# manette_temp.net
KiCad netlist of a schematic drawn in Altium Designer
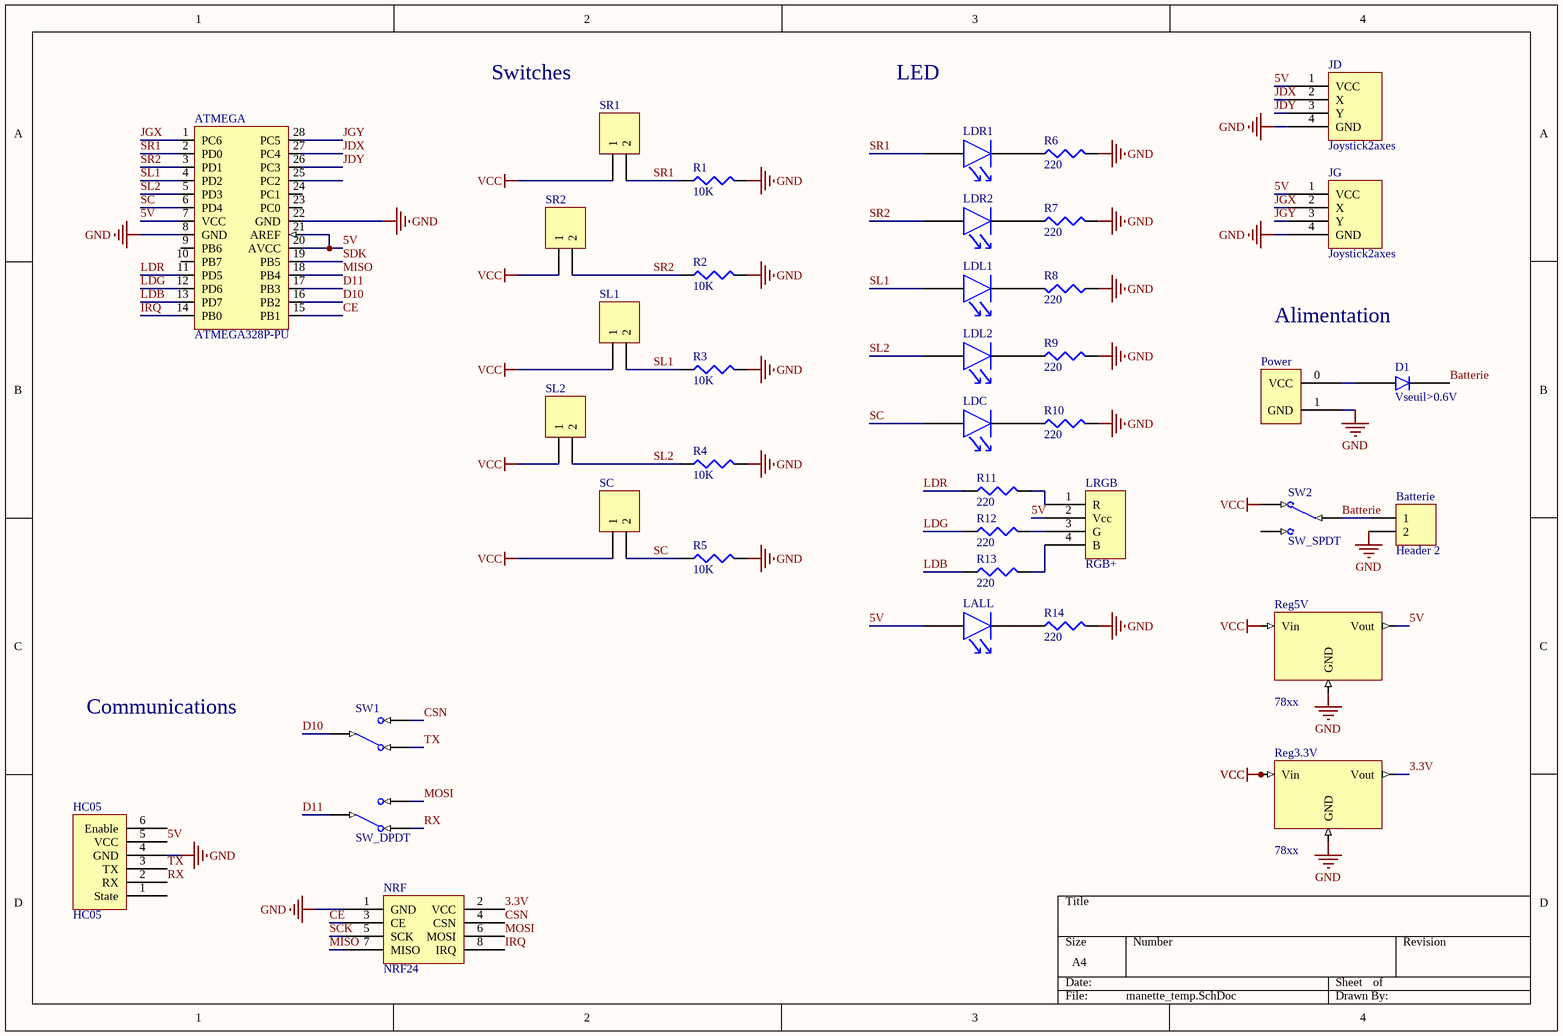
[diagram p0: manette_temp.SchDoc]

(export (version "E")
  (design (tool "Eeschema 10.0.6"))
  (components
    (comp (ref "ATMEGA")
      (value "ATMEGA328P-PU")
      (footprint "DIP28_300")
      (libsource (lib "ISEN_basics") (part "ATMEGA328P-PU"))
    )
    (comp (ref "Batterie")
      (value "Header 2")
      (footprint "HDR1X2")
      (description "Header, 2-Pin")
      (fields (field (name "PUBLISHER") "Altium Limited"))
      (libsource (lib "Miscellaneous Connectors") (part "Header 2"))
    )
    (comp (ref "D1")
      (value "Vseuil>0.6V")
      (footprint "SMA")
      (description "diode usage général")
      (libsource (lib "ISEN_basics") (part "DIODE"))
    )
    (comp (ref "HC05") (value "HC05") (footprint "HC05") (libsource (lib "HC05") (part "HC05")))
    (comp (ref "JD")
      (value "Joystick2axes")
      (footprint "Joystick2axes")
      (libsource (lib "Library") (part "Joystick2axes"))
    )
    (comp (ref "JG")
      (value "Joystick2axes")
      (footprint "Joystick2axes")
      (libsource (lib "Library") (part "Joystick2axes"))
    )
    (comp (ref "LALL")
      (value "comment")
      (footprint "LED5")
      (description "LED 5mm/3mm/CMS")
      (libsource (lib "ISEN_basics") (part "LED"))
    )
    (comp (ref "LDC")
      (value "comment")
      (footprint "LED0805")
      (description "LED 5mm/3mm/CMS")
      (libsource (lib "ISEN_basics") (part "LED"))
    )
    (comp (ref "LDL1")
      (value "comment")
      (footprint "LED0805")
      (description "LED 5mm/3mm/CMS")
      (libsource (lib "ISEN_basics") (part "LED"))
    )
    (comp (ref "LDL2")
      (value "comment")
      (footprint "LED0805")
      (description "LED 5mm/3mm/CMS")
      (libsource (lib "ISEN_basics") (part "LED"))
    )
    (comp (ref "LDR1")
      (value "comment")
      (footprint "LED0805")
      (description "LED 5mm/3mm/CMS")
      (libsource (lib "ISEN_basics") (part "LED"))
    )
    (comp (ref "LDR2")
      (value "comment")
      (footprint "LED0805")
      (description "LED 5mm/3mm/CMS")
      (libsource (lib "ISEN_basics") (part "LED"))
    )
    (comp (ref "LRGB") (value "RGB+") (footprint "Led RGB") (libsource (lib "Library") (part "RGB+")))
    (comp (ref "NRF") (value "NRF24") (footprint "NRF24") (libsource (lib "Library") (part "NRF24")))
    (comp (ref "Power")
      (value "Connecteur Power")
      (footprint "Connecteur Power")
      (libsource (lib "Connectorpower") (part "Connecteur Power"))
    )
    (comp (ref "R1")
      (value "10K")
      (footprint "0805")
      (description "resistance")
      (fields (field (name "Comment") "RES"))
      (libsource (lib "ISEN_basics") (part "RES"))
    )
    (comp (ref "R2")
      (value "10K")
      (footprint "0805")
      (description "resistance")
      (fields (field (name "Comment") "RES"))
      (libsource (lib "ISEN_basics") (part "RES"))
    )
    (comp (ref "R3")
      (value "10K")
      (footprint "0805")
      (description "resistance")
      (fields (field (name "Comment") "RES"))
      (libsource (lib "ISEN_basics") (part "RES"))
    )
    (comp (ref "R4")
      (value "10K")
      (footprint "0805")
      (description "resistance")
      (fields (field (name "Comment") "RES"))
      (libsource (lib "ISEN_basics") (part "RES"))
    )
    (comp (ref "R5")
      (value "10K")
      (footprint "0805")
      (description "resistance")
      (fields (field (name "Comment") "RES"))
      (libsource (lib "ISEN_basics") (part "RES"))
    )
    (comp (ref "R6")
      (value "220")
      (footprint "0805")
      (description "resistance")
      (fields (field (name "Comment") "RES"))
      (libsource (lib "ISEN_basics") (part "RES"))
    )
    (comp (ref "R7")
      (value "220")
      (footprint "0805")
      (description "resistance")
      (fields (field (name "Comment") "RES"))
      (libsource (lib "ISEN_basics") (part "RES"))
    )
    (comp (ref "R8")
      (value "220")
      (footprint "0805")
      (description "resistance")
      (fields (field (name "Comment") "RES"))
      (libsource (lib "ISEN_basics") (part "RES"))
    )
    (comp (ref "R9")
      (value "220")
      (footprint "0805")
      (description "resistance")
      (fields (field (name "Comment") "RES"))
      (libsource (lib "ISEN_basics") (part "RES"))
    )
    (comp (ref "R10")
      (value "220")
      (footprint "0805")
      (description "resistance")
      (fields (field (name "Comment") "RES"))
      (libsource (lib "ISEN_basics") (part "RES"))
    )
    (comp (ref "R11")
      (value "220")
      (footprint "0805")
      (description "resistance")
      (fields (field (name "Comment") "RES"))
      (libsource (lib "ISEN_basics") (part "RES"))
    )
    (comp (ref "R12")
      (value "220")
      (footprint "0805")
      (description "resistance")
      (fields (field (name "Comment") "RES"))
      (libsource (lib "ISEN_basics") (part "RES"))
    )
    (comp (ref "R13")
      (value "220")
      (footprint "0805")
      (description "resistance")
      (fields (field (name "Comment") "RES"))
      (libsource (lib "ISEN_basics") (part "RES"))
    )
    (comp (ref "R14")
      (value "220")
      (footprint "0805")
      (description "resistance")
      (fields (field (name "Comment") "RES"))
      (libsource (lib "ISEN_basics") (part "RES"))
    )
    (comp (ref "Reg3.3V")
      (value "78xx")
      (footprint "TO252")
      (description "régulateur positif fixe")
      (libsource (lib "ISEN_basics") (part "REG_POS"))
    )
    (comp (ref "Reg5V")
      (value "78xx")
      (footprint "TO252")
      (description "régulateur positif fixe")
      (libsource (lib "ISEN_basics") (part "REG_POS"))
    )
    (comp (ref "SC")
      (value "Header 2")
      (footprint "HDR1X2")
      (description "Header, 2-Pin")
      (fields (field (name "PUBLISHER") "Altium Limited"))
      (libsource (lib "") (part "Header 2_1"))
    )
    (comp (ref "SL1")
      (value "Header 2")
      (footprint "HDR1X2")
      (description "Header, 2-Pin")
      (fields (field (name "PUBLISHER") "Altium Limited"))
      (libsource (lib "") (part "Header 2_1"))
    )
    (comp (ref "SL2")
      (value "Header 2")
      (footprint "HDR1X2")
      (description "Header, 2-Pin")
      (fields (field (name "PUBLISHER") "Altium Limited"))
      (libsource (lib "") (part "Header 2_1"))
    )
    (comp (ref "SR1")
      (value "Header 2")
      (footprint "HDR1X2")
      (description "Header, 2-Pin")
      (fields (field (name "PUBLISHER") "Altium Limited"))
      (libsource (lib "") (part "Header 2_1"))
    )
    (comp (ref "SR2")
      (value "Header 2")
      (footprint "HDR1X2")
      (description "Header, 2-Pin")
      (fields (field (name "PUBLISHER") "Altium Limited"))
      (libsource (lib "") (part "Header 2_1"))
    )
    (comp (ref "SW1")
      (value "SW_DPDT")
      (footprint "dpdt_bascule")
      (libsource (lib "ISEN_basics") (part "SW_DPDT"))
    )
    (comp (ref "SW2") (value "SW_SPDT") (footprint "1K2_V") (libsource (lib "ISEN_basics") (part "SW_SPDT")))
  )
  (nets
    (net (code "1") (name "/3.3V") (class "Default")
      (node (ref "NRF") (pin "2") (pinfunction "VCC_2") (pintype "passive"))
      (node (ref "Reg3.3V") (pin "3") (pinfunction "Vout_3") (pintype "output"))
    )
    (net (code "2") (name "/5V") (class "Default")
      (node (ref "ATMEGA") (pin "20") (pinfunction "AVCC_20") (pintype "power_in"))
      (node (ref "ATMEGA") (pin "21") (pinfunction "AREF_21") (pintype "input"))
      (node (ref "ATMEGA") (pin "7") (pinfunction "VCC_7") (pintype "power_in"))
      (node (ref "HC05") (pin "5") (pinfunction "VCC_5") (pintype "passive"))
      (node (ref "JD") (pin "1") (pinfunction "VCC_1") (pintype "passive"))
      (node (ref "JG") (pin "1") (pinfunction "VCC_1") (pintype "passive"))
      (node (ref "LALL") (pin "A") (pinfunction "8_A") (pintype "passive"))
      (node (ref "LRGB") (pin "2") (pinfunction "Vcc_2") (pintype "passive"))
      (node (ref "Reg5V") (pin "3") (pinfunction "Vout_3") (pintype "output"))
    )
    (net (code "3") (name "/Batterie") (class "Default")
      (node (ref "Batterie") (pin "1") (pinfunction "1_1") (pintype "passive"))
      (node (ref "D1") (pin "2") (pinfunction "2_2") (pintype "passive"))
      (node (ref "SW2") (pin "1") (pintype "input"))
    )
    (net (code "4") (name "/CE") (class "Default")
      (node (ref "ATMEGA") (pin "15") (pinfunction "PB1_15") (pintype "bidirectional"))
      (node (ref "NRF") (pin "3") (pinfunction "CE_3") (pintype "passive"))
    )
    (net (code "5") (name "/CSN") (class "Default")
      (node (ref "NRF") (pin "4") (pinfunction "CSN_4") (pintype "passive"))
      (node (ref "SW1") (pin "6") (pinfunction "B_6") (pintype "input"))
    )
    (net (code "6") (name "/D10") (class "Default")
      (node (ref "ATMEGA") (pin "16") (pinfunction "PB2_16") (pintype "bidirectional"))
      (node (ref "SW1") (pin "4") (pintype "input"))
    )
    (net (code "7") (name "/D11") (class "Default")
      (node (ref "ATMEGA") (pin "17") (pinfunction "PB3_17") (pintype "bidirectional"))
      (node (ref "SW1") (pin "1") (pintype "input"))
    )
    (net (code "8") (name "/IRQ") (class "Default")
      (node (ref "ATMEGA") (pin "14") (pinfunction "PB0_14") (pintype "bidirectional"))
      (node (ref "NRF") (pin "8") (pinfunction "IRQ_8") (pintype "passive"))
    )
    (net (code "9") (name "/JDX") (class "Default")
      (node (ref "ATMEGA") (pin "27") (pinfunction "PC4_27") (pintype "bidirectional"))
      (node (ref "JD") (pin "2") (pinfunction "X_2") (pintype "passive"))
    )
    (net (code "10") (name "/JDY") (class "Default")
      (node (ref "ATMEGA") (pin "26") (pinfunction "PC3_26") (pintype "bidirectional"))
      (node (ref "JD") (pin "3") (pinfunction "Y_3") (pintype "passive"))
    )
    (net (code "11") (name "/JGX") (class "Default")
      (node (ref "ATMEGA") (pin "1") (pinfunction "PC6_1") (pintype "bidirectional"))
      (node (ref "JG") (pin "2") (pinfunction "X_2") (pintype "passive"))
    )
    (net (code "12") (name "/JGY") (class "Default")
      (node (ref "ATMEGA") (pin "28") (pinfunction "PC5_28") (pintype "bidirectional"))
      (node (ref "JG") (pin "3") (pinfunction "Y_3") (pintype "passive"))
    )
    (net (code "13") (name "/LDB") (class "Default")
      (node (ref "ATMEGA") (pin "13") (pinfunction "PD7_13") (pintype "bidirectional"))
      (node (ref "R13") (pin "1") (pintype "passive"))
    )
    (net (code "14") (name "/LDG") (class "Default")
      (node (ref "ATMEGA") (pin "12") (pinfunction "PD6_12") (pintype "bidirectional"))
      (node (ref "R12") (pin "1") (pintype "passive"))
    )
    (net (code "15") (name "/LDR") (class "Default")
      (node (ref "ATMEGA") (pin "11") (pinfunction "PD5_11") (pintype "bidirectional"))
      (node (ref "R11") (pin "1") (pintype "passive"))
    )
    (net (code "16") (name "/MISO") (class "Default")
      (node (ref "ATMEGA") (pin "18") (pinfunction "PB4_18") (pintype "bidirectional"))
      (node (ref "NRF") (pin "7") (pinfunction "MISO_7") (pintype "passive"))
    )
    (net (code "17") (name "/MOSI") (class "Default")
      (node (ref "NRF") (pin "6") (pinfunction "MOSI_6") (pintype "passive"))
      (node (ref "SW1") (pin "3") (pinfunction "B_3") (pintype "input"))
    )
    (net (code "18") (name "/RX") (class "Default")
      (node (ref "HC05") (pin "2") (pinfunction "RX_2") (pintype "passive"))
      (node (ref "SW1") (pin "2") (pinfunction "A_2") (pintype "input"))
    )
    (net (code "19") (name "/SC") (class "Default")
      (node (ref "ATMEGA") (pin "6") (pinfunction "PD4_6") (pintype "bidirectional"))
      (node (ref "LDC") (pin "A") (pinfunction "8_A") (pintype "passive"))
      (node (ref "R5") (pin "1") (pintype "passive"))
      (node (ref "SC") (pin "2") (pinfunction "2_2") (pintype "passive"))
    )
    (net (code "20") (name "/SCK") (class "Default")
      (node (ref "NRF") (pin "5") (pinfunction "SCK_5") (pintype "passive"))
    )
    (net (code "21") (name "/SDK") (class "Default")
      (node (ref "ATMEGA") (pin "19") (pinfunction "PB5_19") (pintype "bidirectional"))
    )
    (net (code "22") (name "/SL1") (class "Default")
      (node (ref "ATMEGA") (pin "4") (pinfunction "PD2_4") (pintype "bidirectional"))
      (node (ref "LDL1") (pin "A") (pinfunction "8_A") (pintype "passive"))
      (node (ref "R3") (pin "1") (pintype "passive"))
      (node (ref "SL1") (pin "2") (pinfunction "2_2") (pintype "passive"))
    )
    (net (code "23") (name "/SL2") (class "Default")
      (node (ref "ATMEGA") (pin "5") (pinfunction "PD3_5") (pintype "bidirectional"))
      (node (ref "LDL2") (pin "A") (pinfunction "8_A") (pintype "passive"))
      (node (ref "R4") (pin "1") (pintype "passive"))
      (node (ref "SL2") (pin "2") (pinfunction "2_2") (pintype "passive"))
    )
    (net (code "24") (name "/SR1") (class "Default")
      (node (ref "ATMEGA") (pin "2") (pinfunction "PD0_2") (pintype "bidirectional"))
      (node (ref "LDR1") (pin "A") (pinfunction "8_A") (pintype "passive"))
      (node (ref "R1") (pin "1") (pintype "passive"))
      (node (ref "SR1") (pin "2") (pinfunction "2_2") (pintype "passive"))
    )
    (net (code "25") (name "/SR2") (class "Default")
      (node (ref "ATMEGA") (pin "3") (pinfunction "PD1_3") (pintype "bidirectional"))
      (node (ref "LDR2") (pin "A") (pinfunction "8_A") (pintype "passive"))
      (node (ref "R2") (pin "1") (pintype "passive"))
      (node (ref "SR2") (pin "2") (pinfunction "2_2") (pintype "passive"))
    )
    (net (code "26") (name "/TX") (class "Default")
      (node (ref "HC05") (pin "3") (pinfunction "TX_3") (pintype "passive"))
      (node (ref "SW1") (pin "5") (pinfunction "A_5") (pintype "input"))
    )
    (net (code "27") (name "GND") (class "Default")
      (node (ref "ATMEGA") (pin "22") (pinfunction "GND_22") (pintype "power_in"))
      (node (ref "ATMEGA") (pin "8") (pinfunction "GND_8") (pintype "power_in"))
      (node (ref "Batterie") (pin "2") (pinfunction "2_2") (pintype "passive"))
      (node (ref "HC05") (pin "4") (pinfunction "GND_4") (pintype "passive"))
      (node (ref "JD") (pin "4") (pinfunction "GND_4") (pintype "passive"))
      (node (ref "JG") (pin "4") (pinfunction "GND_4") (pintype "passive"))
      (node (ref "NRF") (pin "1") (pinfunction "GND_1") (pintype "passive"))
      (node (ref "Power") (pin "1") (pinfunction "GND_1") (pintype "passive"))
      (node (ref "R1") (pin "2") (pintype "passive"))
      (node (ref "R10") (pin "2") (pintype "passive"))
      (node (ref "R14") (pin "2") (pintype "passive"))
      (node (ref "R2") (pin "2") (pintype "passive"))
      (node (ref "R3") (pin "2") (pintype "passive"))
      (node (ref "R4") (pin "2") (pintype "passive"))
      (node (ref "R5") (pin "2") (pintype "passive"))
      (node (ref "R6") (pin "2") (pintype "passive"))
      (node (ref "R7") (pin "2") (pintype "passive"))
      (node (ref "R8") (pin "1") (pintype "passive"))
      (node (ref "R9") (pin "2") (pintype "passive"))
      (node (ref "Reg3.3V") (pin "2") (pinfunction "GND_2") (pintype "input"))
      (node (ref "Reg5V") (pin "2") (pinfunction "GND_2") (pintype "input"))
    )
    (net (code "28") (name "Net-(LALL-10)") (class "Default")
      (node (ref "LALL") (pin "K") (pinfunction "10_K") (pintype "passive"))
      (node (ref "R14") (pin "1") (pintype "passive"))
    )
    (net (code "29") (name "Net-(LDC-10)") (class "Default")
      (node (ref "LDC") (pin "K") (pinfunction "10_K") (pintype "passive"))
      (node (ref "R10") (pin "1") (pintype "passive"))
    )
    (net (code "30") (name "Net-(LDL1-10)") (class "Default")
      (node (ref "LDL1") (pin "K") (pinfunction "10_K") (pintype "passive"))
      (node (ref "R8") (pin "2") (pintype "passive"))
    )
    (net (code "31") (name "Net-(LDL2-10)") (class "Default")
      (node (ref "LDL2") (pin "K") (pinfunction "10_K") (pintype "passive"))
      (node (ref "R9") (pin "1") (pintype "passive"))
    )
    (net (code "32") (name "Net-(LDR1-10)") (class "Default")
      (node (ref "LDR1") (pin "K") (pinfunction "10_K") (pintype "passive"))
      (node (ref "R6") (pin "1") (pintype "passive"))
    )
    (net (code "33") (name "Net-(LDR2-10)") (class "Default")
      (node (ref "LDR2") (pin "K") (pinfunction "10_K") (pintype "passive"))
      (node (ref "R7") (pin "1") (pintype "passive"))
    )
    (net (code "34") (name "Net-(LRGB-B)") (class "Default")
      (node (ref "LRGB") (pin "4") (pinfunction "B_4") (pintype "passive"))
      (node (ref "R13") (pin "2") (pintype "passive"))
    )
    (net (code "35") (name "Net-(LRGB-G)") (class "Default")
      (node (ref "LRGB") (pin "3") (pinfunction "G_3") (pintype "passive"))
      (node (ref "R12") (pin "2") (pintype "passive"))
    )
    (net (code "36") (name "Net-(LRGB-R)") (class "Default")
      (node (ref "LRGB") (pin "1") (pinfunction "R_1") (pintype "passive"))
      (node (ref "R11") (pin "2") (pintype "passive"))
    )
    (net (code "37") (name "Net-(Power-VCC)") (class "Default")
      (node (ref "D1") (pin "1") (pinfunction "1_1") (pintype "passive"))
      (node (ref "Power") (pin "0") (pinfunction "VCC_0") (pintype "passive"))
    )
    (net (code "38") (name "VCC") (class "Default")
      (node (ref "Reg3.3V") (pin "1") (pinfunction "Vin_1") (pintype "input"))
      (node (ref "Reg5V") (pin "1") (pinfunction "Vin_1") (pintype "input"))
      (node (ref "SC") (pin "1") (pinfunction "1_1") (pintype "passive"))
      (node (ref "SL1") (pin "1") (pinfunction "1_1") (pintype "passive"))
      (node (ref "SL2") (pin "1") (pinfunction "1_1") (pintype "passive"))
      (node (ref "SR1") (pin "1") (pinfunction "1_1") (pintype "passive"))
      (node (ref "SR2") (pin "1") (pinfunction "1_1") (pintype "passive"))
      (node (ref "SW2") (pin "2") (pinfunction "A_2") (pintype "input"))
    )
    (net (code "39") (name "unconnected-(ATMEGA-PB6-Pad9)") (class "Default")
      (node (ref "ATMEGA") (pin "9") (pinfunction "PB6_9") (pintype "bidirectional"))
    )
    (net (code "40") (name "unconnected-(ATMEGA-PB7-Pad10)") (class "Default")
      (node (ref "ATMEGA") (pin "10") (pinfunction "PB7_10") (pintype "bidirectional"))
    )
    (net (code "41") (name "unconnected-(ATMEGA-PC0-Pad23)") (class "Default")
      (node (ref "ATMEGA") (pin "23") (pinfunction "PC0_23") (pintype "bidirectional"))
    )
    (net (code "42") (name "unconnected-(ATMEGA-PC1-Pad24)") (class "Default")
      (node (ref "ATMEGA") (pin "24") (pinfunction "PC1_24") (pintype "bidirectional"))
    )
    (net (code "43") (name "unconnected-(ATMEGA-PC2-Pad25)") (class "Default")
      (node (ref "ATMEGA") (pin "25") (pinfunction "PC2_25") (pintype "bidirectional"))
    )
    (net (code "44") (name "unconnected-(HC05-Enable-Pad6)") (class "Default")
      (node (ref "HC05") (pin "6") (pinfunction "Enable_6") (pintype "passive"))
    )
    (net (code "45") (name "unconnected-(HC05-State-Pad1)") (class "Default")
      (node (ref "HC05") (pin "1") (pinfunction "State_1") (pintype "passive"))
    )
    (net (code "46") (name "unconnected-(SW2-B-Pad3)") (class "Default")
      (node (ref "SW2") (pin "3") (pinfunction "B_3") (pintype "input"))
    )
  )
)
